# gm-board.net
KiCad netlist of a schematic drawn in EAGLE
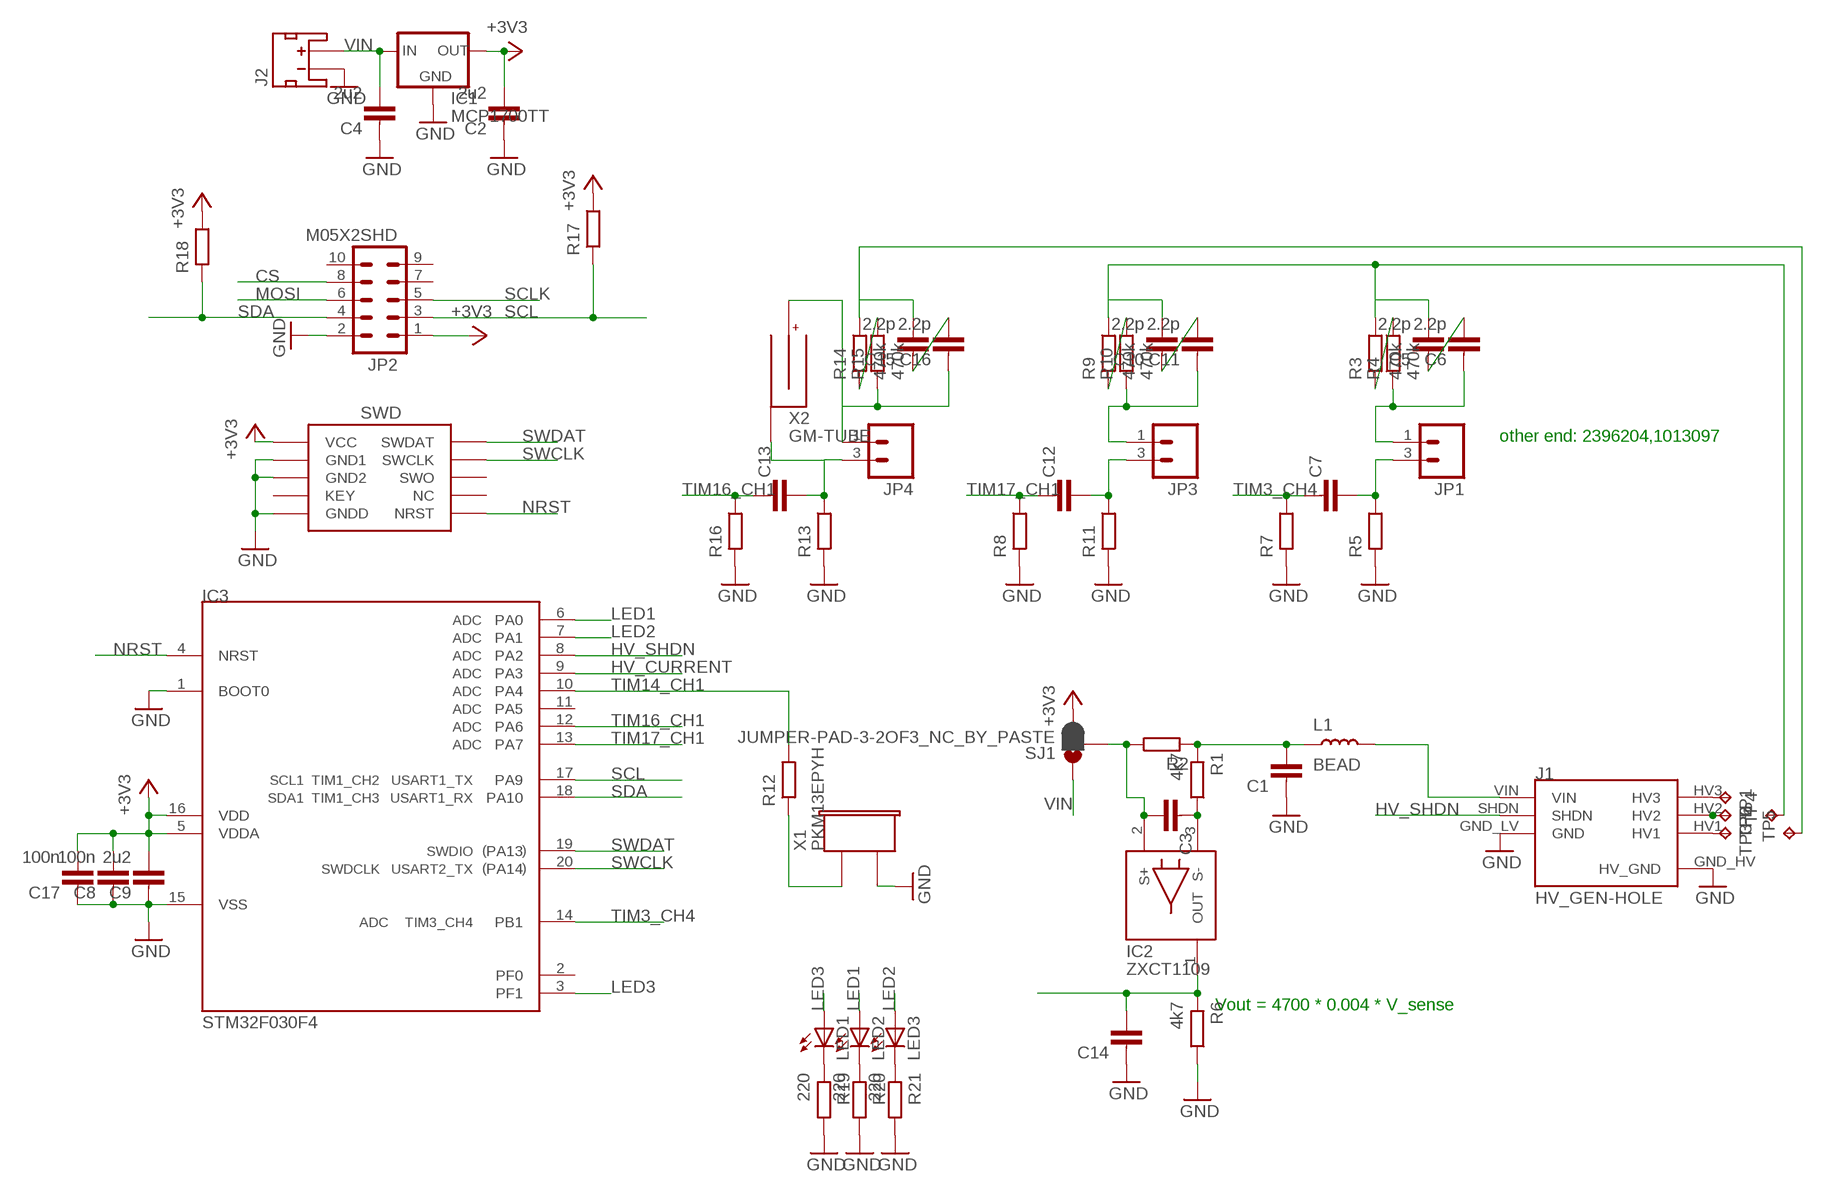
[diagram p0: schematic, sheet 1]

(export (version "E")
  (design (tool "Eeschema 10.0.6"))
  (components
    (comp (ref "C1")
      (value "CAPACITOR0603-N")
      (footprint "eagle-import:C0603-N")
      (libsource (lib "eagle-import") (part "CAPACITOR0603-N"))
    )
    (comp (ref "C2")
      (value "2u2")
      (footprint "eagle-import:C0603-N")
      (libsource (lib "eagle-import") (part "CAPACITOR0603-N"))
    )
    (comp (ref "C3")
      (value "CAPACITOR0603-N")
      (footprint "eagle-import:C0603-N")
      (libsource (lib "eagle-import") (part "CAPACITOR0603-N"))
    )
    (comp (ref "C4")
      (value "2u2")
      (footprint "eagle-import:C0603-N")
      (libsource (lib "eagle-import") (part "CAPACITOR0603-N"))
    )
    (comp (ref "C5")
      (value "2.2p")
      (footprint "eagle-import:C0805-N")
      (libsource (lib "eagle-import") (part "CAPACITOR0805-N"))
    )
    (comp (ref "C6")
      (value "2.2p")
      (footprint "eagle-import:C0805-N")
      (libsource (lib "eagle-import") (part "CAPACITOR0805-N"))
    )
    (comp (ref "C7")
      (value "CAPACITOR0603-N")
      (footprint "eagle-import:C0603-N")
      (libsource (lib "eagle-import") (part "CAPACITOR0603-N"))
    )
    (comp (ref "C8")
      (value "100n")
      (footprint "eagle-import:C0603-N")
      (libsource (lib "eagle-import") (part "CAPACITOR0603-N"))
    )
    (comp (ref "C9")
      (value "2u2")
      (footprint "eagle-import:C0603-N")
      (libsource (lib "eagle-import") (part "CAPACITOR0603-N"))
    )
    (comp (ref "C10")
      (value "2.2p")
      (footprint "eagle-import:C0805-N")
      (libsource (lib "eagle-import") (part "CAPACITOR0805-N"))
    )
    (comp (ref "C11")
      (value "2.2p")
      (footprint "eagle-import:C0805-N")
      (libsource (lib "eagle-import") (part "CAPACITOR0805-N"))
    )
    (comp (ref "C12")
      (value "CAPACITOR0603-N")
      (footprint "eagle-import:C0603-N")
      (libsource (lib "eagle-import") (part "CAPACITOR0603-N"))
    )
    (comp (ref "C13")
      (value "CAPACITOR0603-N")
      (footprint "eagle-import:C0603-N")
      (libsource (lib "eagle-import") (part "CAPACITOR0603-N"))
    )
    (comp (ref "C14")
      (value "CAPACITOR0603-N")
      (footprint "eagle-import:C0603-N")
      (libsource (lib "eagle-import") (part "CAPACITOR0603-N"))
    )
    (comp (ref "C15")
      (value "2.2p")
      (footprint "eagle-import:C0805-N")
      (libsource (lib "eagle-import") (part "CAPACITOR0805-N"))
    )
    (comp (ref "C16")
      (value "2.2p")
      (footprint "eagle-import:C0805-N")
      (libsource (lib "eagle-import") (part "CAPACITOR0805-N"))
    )
    (comp (ref "C17")
      (value "100n")
      (footprint "eagle-import:C0603-N")
      (libsource (lib "eagle-import") (part "CAPACITOR0603-N"))
    )
    (comp (ref "IC1")
      (value "MCP1700TT")
      (footprint "eagle-import:SOT23")
      (libsource (lib "eagle-import") (part "MCP1700TT"))
    )
    (comp (ref "IC2")
      (value "ZXCT1109")
      (footprint "eagle-import:SOT23")
      (libsource (lib "eagle-import") (part "ZXCT1109"))
    )
    (comp (ref "IC3")
      (value "STM32F030F4")
      (footprint "eagle-import:TSSOP20")
      (libsource (lib "eagle-import") (part "STM32F030F4"))
    )
    (comp (ref "J1")
      (value "HV_GEN-HOLE")
      (footprint "eagle-import:BRD-LAYOUT2")
      (libsource (lib "eagle-import") (part "HV_GEN-HOLE"))
    )
    (comp (ref "J2")
      (value "JST_2MM_MALE_TH-NT")
      (footprint "eagle-import:JST-2-TH-NOTEXT")
      (libsource (lib "eagle-import") (part "JST_2MM_MALE_TH-NT"))
    )
    (comp (ref "J3")
      (value "SWD_SHROUD")
      (footprint "eagle-import:SWD_PTH_SHROUD")
      (libsource (lib "eagle-import") (part "SWD_SHROUD"))
    )
    (comp (ref "JP1")
      (value "M02-HV")
      (footprint "eagle-import:M03-HV")
      (libsource (lib "eagle-import") (part "M02-HV"))
    )
    (comp (ref "JP2")
      (value "M05X2SHD")
      (footprint "eagle-import:2X5-SHROUDED")
      (libsource (lib "eagle-import") (part "M05X2SHD"))
    )
    (comp (ref "JP3")
      (value "M02-HV")
      (footprint "eagle-import:M03-HV")
      (libsource (lib "eagle-import") (part "M02-HV"))
    )
    (comp (ref "JP4")
      (value "M02-HV")
      (footprint "eagle-import:M03-HV")
      (libsource (lib "eagle-import") (part "M02-HV"))
    )
    (comp (ref "L1")
      (value "BEAD")
      (footprint "eagle-import:L0603-N")
      (libsource (lib "eagle-import") (part "INDUCTOR0603-N"))
    )
    (comp (ref "LED1")
      (value "LEDCHIPLED_0603")
      (footprint "eagle-import:CHIPLED_0603")
      (libsource (lib "eagle-import") (part "LEDCHIPLED_0603"))
    )
    (comp (ref "LED2")
      (value "LEDCHIPLED_0603")
      (footprint "eagle-import:CHIPLED_0603")
      (libsource (lib "eagle-import") (part "LEDCHIPLED_0603"))
    )
    (comp (ref "LED3")
      (value "LEDCHIPLED_0603")
      (footprint "eagle-import:CHIPLED_0603")
      (libsource (lib "eagle-import") (part "LEDCHIPLED_0603"))
    )
    (comp (ref "R1")
      (value "4k7")
      (footprint "eagle-import:R0603-N")
      (libsource (lib "eagle-import") (part "RESISTOR0603-N"))
    )
    (comp (ref "R2")
      (value "RESISTOR0603-N")
      (footprint "eagle-import:R0603-N")
      (libsource (lib "eagle-import") (part "RESISTOR0603-N"))
    )
    (comp (ref "R3")
      (value "470k")
      (footprint "eagle-import:R1206-N")
      (libsource (lib "eagle-import") (part "RESISTOR1206-N"))
    )
    (comp (ref "R4")
      (value "470k")
      (footprint "eagle-import:R1206-N")
      (libsource (lib "eagle-import") (part "RESISTOR1206-N"))
    )
    (comp (ref "R5")
      (value "RESISTOR0603-N")
      (footprint "eagle-import:R0603-N")
      (libsource (lib "eagle-import") (part "RESISTOR0603-N"))
    )
    (comp (ref "R6")
      (value "4k7")
      (footprint "eagle-import:R0603-N")
      (libsource (lib "eagle-import") (part "RESISTOR0603-N"))
    )
    (comp (ref "R7")
      (value "RESISTOR0603-N")
      (footprint "eagle-import:R0603-N")
      (libsource (lib "eagle-import") (part "RESISTOR0603-N"))
    )
    (comp (ref "R8")
      (value "RESISTOR0603-N")
      (footprint "eagle-import:R0603-N")
      (libsource (lib "eagle-import") (part "RESISTOR0603-N"))
    )
    (comp (ref "R9")
      (value "470k")
      (footprint "eagle-import:R1206-N")
      (libsource (lib "eagle-import") (part "RESISTOR1206-N"))
    )
    (comp (ref "R10")
      (value "470k")
      (footprint "eagle-import:R1206-N")
      (libsource (lib "eagle-import") (part "RESISTOR1206-N"))
    )
    (comp (ref "R11")
      (value "RESISTOR0603-N")
      (footprint "eagle-import:R0603-N")
      (libsource (lib "eagle-import") (part "RESISTOR0603-N"))
    )
    (comp (ref "R12")
      (value "RESISTOR0603-N")
      (footprint "eagle-import:R0603-N")
      (libsource (lib "eagle-import") (part "RESISTOR0603-N"))
    )
    (comp (ref "R13")
      (value "RESISTOR0603-N")
      (footprint "eagle-import:R0603-N")
      (libsource (lib "eagle-import") (part "RESISTOR0603-N"))
    )
    (comp (ref "R14")
      (value "470k")
      (footprint "eagle-import:R1206-N")
      (libsource (lib "eagle-import") (part "RESISTOR1206-N"))
    )
    (comp (ref "R15")
      (value "470k")
      (footprint "eagle-import:R1206-N")
      (libsource (lib "eagle-import") (part "RESISTOR1206-N"))
    )
    (comp (ref "R16")
      (value "RESISTOR0603-N")
      (footprint "eagle-import:R0603-N")
      (libsource (lib "eagle-import") (part "RESISTOR0603-N"))
    )
    (comp (ref "R17")
      (value "RESISTOR0603-N")
      (footprint "eagle-import:R0603-N")
      (libsource (lib "eagle-import") (part "RESISTOR0603-N"))
    )
    (comp (ref "R18")
      (value "RESISTOR0603-N")
      (footprint "eagle-import:R0603-N")
      (libsource (lib "eagle-import") (part "RESISTOR0603-N"))
    )
    (comp (ref "R19")
      (value "220")
      (footprint "eagle-import:R0603-N")
      (libsource (lib "eagle-import") (part "RESISTOR0603-N"))
    )
    (comp (ref "R20")
      (value "220")
      (footprint "eagle-import:R0603-N")
      (libsource (lib "eagle-import") (part "RESISTOR0603-N"))
    )
    (comp (ref "R21")
      (value "220")
      (footprint "eagle-import:R0603-N")
      (libsource (lib "eagle-import") (part "RESISTOR0603-N"))
    )
    (comp (ref "SJ1")
      (value "JUMPER-PAD-3-2OF3_NC_BY_PASTE")
      (footprint "eagle-import:PAD-JUMPER-3-2OF3_NC_BY_PASTE_YES_SILK_FULL_BOX")
      (libsource (lib "eagle-import") (part "JUMPER-PAD-3-2OF3_NC_BY_PASTE"))
    )
    (comp (ref "TP1")
      (value "TPTP09R")
      (footprint "eagle-import:TP09R")
      (libsource (lib "eagle-import") (part "TPTP09R"))
    )
    (comp (ref "TP2")
      (value "TPTP09R")
      (footprint "eagle-import:TP09R")
      (libsource (lib "eagle-import") (part "TPTP09R"))
    )
    (comp (ref "TP3")
      (value "TPTP09R")
      (footprint "eagle-import:TP09R")
      (libsource (lib "eagle-import") (part "TPTP09R"))
    )
    (comp (ref "TP4")
      (value "TPTP09R")
      (footprint "eagle-import:TP09R")
      (libsource (lib "eagle-import") (part "TPTP09R"))
    )
    (comp (ref "TP5")
      (value "TPTP09R")
      (footprint "eagle-import:TP09R")
      (libsource (lib "eagle-import") (part "TPTP09R"))
    )
    (comp (ref "TP6")
      (value "TPTP09R")
      (footprint "eagle-import:TP09R")
      (libsource (lib "eagle-import") (part "TPTP09R"))
    )
    (comp (ref "X1")
      (value "PKM13EPYH")
      (footprint "eagle-import:PKM13EPYH")
      (libsource (lib "eagle-import") (part "PKM13EPYH"))
    )
    (comp (ref "X2")
      (value "GM-TUBE")
      (footprint "eagle-import:GM-TUBE")
      (libsource (lib "eagle-import") (part "GM-TUBE"))
    )
  )
  (nets
    (net (code "1") (name "+3V3") (class "Default")
      (node (ref "C17") (pin "2") (pinfunction "2_2") (pintype "passive"))
      (node (ref "C2") (pin "2") (pinfunction "2_2") (pintype "passive"))
      (node (ref "C8") (pin "2") (pinfunction "2_2") (pintype "passive"))
      (node (ref "C9") (pin "2") (pinfunction "2_2") (pintype "passive"))
      (node (ref "IC1") (pin "2") (pinfunction "OUT_2") (pintype "passive"))
      (node (ref "IC3") (pin "16") (pinfunction "VDD_16") (pintype "power_in"))
      (node (ref "IC3") (pin "5") (pinfunction "VDDA_5") (pintype "power_in"))
      (node (ref "J3") (pin "1") (pinfunction "VCC_1") (pintype "power_in"))
      (node (ref "JP2") (pin "1") (pinfunction "1_1") (pintype "passive"))
      (node (ref "R17") (pin "2") (pinfunction "P$2_2") (pintype "passive"))
      (node (ref "R18") (pin "2") (pinfunction "P$2_2") (pintype "passive"))
      (node (ref "SJ1") (pin "3") (pinfunction "3_3") (pintype "passive"))
    )
    (net (code "2") (name "/CS") (class "Default")
      (node (ref "JP2") (pin "8") (pinfunction "8_8") (pintype "passive"))
    )
    (net (code "3") (name "/HV_CURRENT") (class "Default")
      (node (ref "C14") (pin "2") (pinfunction "2_2") (pintype "passive"))
      (node (ref "IC2") (pin "1") (pinfunction "OUT_1") (pintype "output"))
      (node (ref "IC3") (pin "9") (pinfunction "PA3_9") (pintype "bidirectional"))
      (node (ref "R6") (pin "1") (pinfunction "P$1_1") (pintype "passive"))
    )
    (net (code "4") (name "/HV_SHDN") (class "Default")
      (node (ref "IC3") (pin "8") (pinfunction "PA2_8") (pintype "bidirectional"))
      (node (ref "J1") (pin "SHDN") (pinfunction "SHDN_SHDN") (pintype "bidirectional"))
    )
    (net (code "5") (name "/LED1") (class "Default")
      (node (ref "IC3") (pin "6") (pinfunction "PA0_6") (pintype "bidirectional"))
      (node (ref "LED2") (pin "A") (pinfunction "A_A") (pintype "passive"))
    )
    (net (code "6") (name "/LED2") (class "Default")
      (node (ref "IC3") (pin "7") (pinfunction "PA1_7") (pintype "bidirectional"))
      (node (ref "LED3") (pin "A") (pinfunction "A_A") (pintype "passive"))
    )
    (net (code "7") (name "/LED3") (class "Default")
      (node (ref "IC3") (pin "3") (pinfunction "PF1_3") (pintype "bidirectional"))
      (node (ref "LED1") (pin "A") (pinfunction "A_A") (pintype "passive"))
    )
    (net (code "8") (name "/MOSI") (class "Default")
      (node (ref "JP2") (pin "6") (pinfunction "6_6") (pintype "passive"))
    )
    (net (code "9") (name "/NRST") (class "Default")
      (node (ref "IC3") (pin "4") (pinfunction "NRST_4") (pintype "input"))
      (node (ref "J3") (pin "10") (pinfunction "NRST_10") (pintype "bidirectional"))
    )
    (net (code "10") (name "/SCL") (class "Default")
      (node (ref "IC3") (pin "17") (pinfunction "PA9_17") (pintype "bidirectional"))
      (node (ref "JP2") (pin "3") (pinfunction "3_3") (pintype "passive"))
      (node (ref "R17") (pin "1") (pinfunction "P$1_1") (pintype "passive"))
    )
    (net (code "11") (name "/SCLK") (class "Default")
      (node (ref "JP2") (pin "5") (pinfunction "5_5") (pintype "passive"))
    )
    (net (code "12") (name "/SDA") (class "Default")
      (node (ref "IC3") (pin "18") (pinfunction "PA10_18") (pintype "bidirectional"))
      (node (ref "JP2") (pin "4") (pinfunction "4_4") (pintype "passive"))
      (node (ref "R18") (pin "1") (pinfunction "P$1_1") (pintype "passive"))
    )
    (net (code "13") (name "/SWCLK") (class "Default")
      (node (ref "IC3") (pin "20") (pinfunction "PA14_20") (pintype "bidirectional"))
      (node (ref "J3") (pin "4") (pinfunction "SWCLK_4") (pintype "bidirectional"))
    )
    (net (code "14") (name "/SWDAT") (class "Default")
      (node (ref "IC3") (pin "19") (pinfunction "PA13_19") (pintype "bidirectional"))
      (node (ref "J3") (pin "2") (pinfunction "SWDAT_2") (pintype "bidirectional"))
    )
    (net (code "15") (name "/TIM3_CH4") (class "Default")
      (node (ref "C7") (pin "1") (pinfunction "1_1") (pintype "passive"))
      (node (ref "IC3") (pin "14") (pinfunction "PB1_14") (pintype "bidirectional"))
      (node (ref "R7") (pin "2") (pinfunction "P$2_2") (pintype "passive"))
    )
    (net (code "16") (name "/TIM14_CH1") (class "Default")
      (node (ref "IC3") (pin "10") (pinfunction "PA4_10") (pintype "bidirectional"))
      (node (ref "R12") (pin "2") (pinfunction "P$2_2") (pintype "passive"))
    )
    (net (code "17") (name "/TIM16_CH1") (class "Default")
      (node (ref "C13") (pin "1") (pinfunction "1_1") (pintype "passive"))
      (node (ref "IC3") (pin "12") (pinfunction "PA6_12") (pintype "bidirectional"))
      (node (ref "R16") (pin "2") (pinfunction "P$2_2") (pintype "passive"))
    )
    (net (code "18") (name "/TIM17_CH1") (class "Default")
      (node (ref "C12") (pin "1") (pinfunction "1_1") (pintype "passive"))
      (node (ref "IC3") (pin "13") (pinfunction "PA7_13") (pintype "bidirectional"))
      (node (ref "R8") (pin "2") (pinfunction "P$2_2") (pintype "passive"))
    )
    (net (code "19") (name "/VIN") (class "Default")
      (node (ref "C4") (pin "2") (pinfunction "2_2") (pintype "passive"))
      (node (ref "IC1") (pin "3") (pinfunction "IN_3") (pintype "input"))
      (node (ref "J2") (pin "1") (pinfunction "+_1") (pintype "bidirectional"))
      (node (ref "SJ1") (pin "1") (pinfunction "1_1") (pintype "passive"))
    )
    (net (code "20") (name "GND") (class "Default")
      (node (ref "C1") (pin "1") (pinfunction "1_1") (pintype "passive"))
      (node (ref "C14") (pin "1") (pinfunction "1_1") (pintype "passive"))
      (node (ref "C17") (pin "1") (pinfunction "1_1") (pintype "passive"))
      (node (ref "C2") (pin "1") (pinfunction "1_1") (pintype "passive"))
      (node (ref "C4") (pin "1") (pinfunction "1_1") (pintype "passive"))
      (node (ref "C8") (pin "1") (pinfunction "1_1") (pintype "passive"))
      (node (ref "C9") (pin "1") (pinfunction "1_1") (pintype "passive"))
      (node (ref "IC1") (pin "1") (pinfunction "GND_1") (pintype "input"))
      (node (ref "IC3") (pin "1") (pinfunction "BOOT0_1") (pintype "input"))
      (node (ref "IC3") (pin "15") (pinfunction "VSS_15") (pintype "power_in"))
      (node (ref "J1") (pin "GND_HV") (pinfunction "HV_GND_GND_HV") (pintype "bidirectional"))
      (node (ref "J1") (pin "GND_LV") (pinfunction "GND_GND_LV") (pintype "bidirectional"))
      (node (ref "J2") (pin "2") (pinfunction "-_2") (pintype "bidirectional"))
      (node (ref "J3") (pin "3") (pinfunction "GND1_3") (pintype "power_in"))
      (node (ref "J3") (pin "5") (pinfunction "GND2_5") (pintype "power_in"))
      (node (ref "J3") (pin "9") (pinfunction "GNDD_9") (pintype "power_in"))
      (node (ref "JP2") (pin "2") (pinfunction "2_2") (pintype "passive"))
      (node (ref "R11") (pin "1") (pinfunction "P$1_1") (pintype "passive"))
      (node (ref "R13") (pin "1") (pinfunction "P$1_1") (pintype "passive"))
      (node (ref "R16") (pin "1") (pinfunction "P$1_1") (pintype "passive"))
      (node (ref "R19") (pin "2") (pinfunction "P$2_2") (pintype "passive"))
      (node (ref "R20") (pin "2") (pinfunction "P$2_2") (pintype "passive"))
      (node (ref "R21") (pin "2") (pinfunction "P$2_2") (pintype "passive"))
      (node (ref "R5") (pin "1") (pinfunction "P$1_1") (pintype "passive"))
      (node (ref "R6") (pin "2") (pinfunction "P$2_2") (pintype "passive"))
      (node (ref "R7") (pin "1") (pinfunction "P$1_1") (pintype "passive"))
      (node (ref "R8") (pin "1") (pinfunction "P$1_1") (pintype "passive"))
      (node (ref "X1") (pin "2") (pinfunction "2_2") (pintype "bidirectional"))
    )
    (net (code "21") (name "Net-(C5-Pad1)") (class "Default")
      (node (ref "C5") (pin "1") (pinfunction "1_1") (pintype "passive"))
      (node (ref "C6") (pin "2") (pinfunction "2_2") (pintype "passive"))
    )
    (net (code "22") (name "Net-(C10-Pad1)") (class "Default")
      (node (ref "C10") (pin "1") (pinfunction "1_1") (pintype "passive"))
      (node (ref "C11") (pin "2") (pinfunction "2_2") (pintype "passive"))
    )
    (net (code "23") (name "Net-(C15-Pad1)") (class "Default")
      (node (ref "C15") (pin "1") (pinfunction "1_1") (pintype "passive"))
      (node (ref "C16") (pin "2") (pinfunction "2_2") (pintype "passive"))
    )
    (net (code "24") (name "Net-(IC2-S+)") (class "Default")
      (node (ref "C3") (pin "2") (pinfunction "2_2") (pintype "passive"))
      (node (ref "IC2") (pin "2") (pinfunction "S+_2") (pintype "input"))
      (node (ref "R2") (pin "2") (pinfunction "P$2_2") (pintype "passive"))
      (node (ref "SJ1") (pin "2") (pinfunction "2_2") (pintype "passive"))
    )
    (net (code "25") (name "Net-(IC2-S-)") (class "Default")
      (node (ref "C3") (pin "1") (pinfunction "1_1") (pintype "passive"))
      (node (ref "IC2") (pin "3") (pinfunction "S-_3") (pintype "input"))
      (node (ref "R1") (pin "2") (pinfunction "P$2_2") (pintype "passive"))
    )
    (net (code "26") (name "Net-(J1-PadHV1)") (class "Default")
      (node (ref "J1") (pin "HV1") (pinfunction "HV1_HV1") (pintype "bidirectional"))
      (node (ref "TP3") (pin "TP") (pinfunction "TP_TP") (pintype "input"))
    )
    (net (code "27") (name "Net-(J1-PadHV2)") (class "Default")
      (node (ref "J1") (pin "HV2") (pinfunction "HV2_HV2") (pintype "bidirectional"))
      (node (ref "TP2") (pin "TP") (pinfunction "TP_TP") (pintype "input"))
      (node (ref "TP6") (pin "TP") (pinfunction "TP_TP") (pintype "input"))
    )
    (net (code "28") (name "Net-(J1-PadHV3)") (class "Default")
      (node (ref "J1") (pin "HV3") (pinfunction "HV3_HV3") (pintype "bidirectional"))
      (node (ref "TP1") (pin "TP") (pinfunction "TP_TP") (pintype "input"))
    )
    (net (code "29") (name "Net-(JP1-2)") (class "Default")
      (node (ref "C7") (pin "2") (pinfunction "2_2") (pintype "passive"))
      (node (ref "JP1") (pin "3") (pinfunction "2_3") (pintype "passive"))
      (node (ref "R5") (pin "2") (pinfunction "P$2_2") (pintype "passive"))
    )
    (net (code "30") (name "Net-(JP3-2)") (class "Default")
      (node (ref "C12") (pin "2") (pinfunction "2_2") (pintype "passive"))
      (node (ref "JP3") (pin "3") (pinfunction "2_3") (pintype "passive"))
      (node (ref "R11") (pin "2") (pinfunction "P$2_2") (pintype "passive"))
    )
    (net (code "31") (name "Net-(JP4-2)") (class "Default")
      (node (ref "C13") (pin "2") (pinfunction "2_2") (pintype "passive"))
      (node (ref "JP4") (pin "3") (pinfunction "2_3") (pintype "passive"))
      (node (ref "R13") (pin "2") (pinfunction "P$2_2") (pintype "passive"))
      (node (ref "X2") (pin "B1") (pinfunction "-_B1") (pintype "bidirectional"))
      (node (ref "X2") (pin "B2") (pinfunction "-_B2") (pintype "bidirectional"))
    )
    (net (code "32") (name "Net-(L1-P$1)") (class "Default")
      (node (ref "C1") (pin "2") (pinfunction "2_2") (pintype "passive"))
      (node (ref "L1") (pin "1") (pinfunction "P$1_1") (pintype "passive"))
      (node (ref "R1") (pin "1") (pinfunction "P$1_1") (pintype "passive"))
      (node (ref "R2") (pin "1") (pinfunction "P$1_1") (pintype "passive"))
    )
    (net (code "33") (name "Net-(L1-P$2)") (class "Default")
      (node (ref "J1") (pin "VIN") (pinfunction "VIN_VIN") (pintype "bidirectional"))
      (node (ref "L1") (pin "2") (pinfunction "P$2_2") (pintype "passive"))
    )
    (net (code "34") (name "Net-(R3-P$1)") (class "Default")
      (node (ref "R3") (pin "1") (pinfunction "P$1_1") (pintype "passive"))
      (node (ref "R4") (pin "2") (pinfunction "P$2_2") (pintype "passive"))
    )
    (net (code "35") (name "Net-(R3-P$2)") (class "Default")
      (node (ref "C10") (pin "2") (pinfunction "2_2") (pintype "passive"))
      (node (ref "C5") (pin "2") (pinfunction "2_2") (pintype "passive"))
      (node (ref "R3") (pin "2") (pinfunction "P$2_2") (pintype "passive"))
      (node (ref "R9") (pin "2") (pinfunction "P$2_2") (pintype "passive"))
      (node (ref "TP4") (pin "TP") (pinfunction "TP_TP") (pintype "input"))
    )
    (net (code "36") (name "Net-(R4-P$1)") (class "Default")
      (node (ref "C6") (pin "1") (pinfunction "1_1") (pintype "passive"))
      (node (ref "JP1") (pin "1") (pinfunction "1_1") (pintype "passive"))
      (node (ref "R4") (pin "1") (pinfunction "P$1_1") (pintype "passive"))
    )
    (net (code "37") (name "Net-(R10-P$1)") (class "Default")
      (node (ref "C11") (pin "1") (pinfunction "1_1") (pintype "passive"))
      (node (ref "JP3") (pin "1") (pinfunction "1_1") (pintype "passive"))
      (node (ref "R10") (pin "1") (pinfunction "P$1_1") (pintype "passive"))
    )
    (net (code "38") (name "Net-(R10-P$2)") (class "Default")
      (node (ref "R10") (pin "2") (pinfunction "P$2_2") (pintype "passive"))
      (node (ref "R9") (pin "1") (pinfunction "P$1_1") (pintype "passive"))
    )
    (net (code "39") (name "Net-(R12-P$1)") (class "Default")
      (node (ref "R12") (pin "1") (pinfunction "P$1_1") (pintype "passive"))
      (node (ref "X1") (pin "1") (pinfunction "1_1") (pintype "bidirectional"))
    )
    (net (code "40") (name "Net-(R14-P$1)") (class "Default")
      (node (ref "R14") (pin "1") (pinfunction "P$1_1") (pintype "passive"))
      (node (ref "R15") (pin "2") (pinfunction "P$2_2") (pintype "passive"))
    )
    (net (code "41") (name "Net-(R14-P$2)") (class "Default")
      (node (ref "C15") (pin "2") (pinfunction "2_2") (pintype "passive"))
      (node (ref "R14") (pin "2") (pinfunction "P$2_2") (pintype "passive"))
      (node (ref "TP5") (pin "TP") (pinfunction "TP_TP") (pintype "input"))
    )
    (net (code "42") (name "Net-(R15-P$1)") (class "Default")
      (node (ref "C16") (pin "1") (pinfunction "1_1") (pintype "passive"))
      (node (ref "JP4") (pin "1") (pinfunction "1_1") (pintype "passive"))
      (node (ref "R15") (pin "1") (pinfunction "P$1_1") (pintype "passive"))
      (node (ref "X2") (pin "A1") (pinfunction "+_A1") (pintype "bidirectional"))
      (node (ref "X2") (pin "A2") (pinfunction "+_A2") (pintype "bidirectional"))
    )
    (net (code "43") (name "Net-(R19-P$1)") (class "Default")
      (node (ref "LED1") (pin "C") (pinfunction "C_C") (pintype "passive"))
      (node (ref "R19") (pin "1") (pinfunction "P$1_1") (pintype "passive"))
    )
    (net (code "44") (name "Net-(R20-P$1)") (class "Default")
      (node (ref "LED2") (pin "C") (pinfunction "C_C") (pintype "passive"))
      (node (ref "R20") (pin "1") (pinfunction "P$1_1") (pintype "passive"))
    )
    (net (code "45") (name "Net-(R21-P$1)") (class "Default")
      (node (ref "LED3") (pin "C") (pinfunction "C_C") (pintype "passive"))
      (node (ref "R21") (pin "1") (pinfunction "P$1_1") (pintype "passive"))
    )
    (net (code "46") (name "unconnected-(IC3-PA5-Pad11)") (class "Default")
      (node (ref "IC3") (pin "11") (pinfunction "PA5_11") (pintype "bidirectional"))
    )
    (net (code "47") (name "unconnected-(IC3-PF0-Pad2)") (class "Default")
      (node (ref "IC3") (pin "2") (pinfunction "PF0_2") (pintype "bidirectional"))
    )
    (net (code "48") (name "unconnected-(J3-KEY-Pad7)") (class "Default")
      (node (ref "J3") (pin "7") (pinfunction "KEY_7") (pintype "bidirectional"))
    )
    (net (code "49") (name "unconnected-(J3-NC-Pad8)") (class "Default")
      (node (ref "J3") (pin "8") (pinfunction "NC_8") (pintype "no_connect"))
    )
    (net (code "50") (name "unconnected-(J3-SWO-Pad6)") (class "Default")
      (node (ref "J3") (pin "6") (pinfunction "SWO_6") (pintype "bidirectional"))
    )
    (net (code "51") (name "unconnected-(JP2-Pad7)") (class "Default")
      (node (ref "JP2") (pin "7") (pinfunction "7_7") (pintype "passive"))
    )
    (net (code "52") (name "unconnected-(JP2-Pad9)") (class "Default")
      (node (ref "JP2") (pin "9") (pinfunction "9_9") (pintype "passive"))
    )
    (net (code "53") (name "unconnected-(JP2-Pad10)") (class "Default")
      (node (ref "JP2") (pin "10") (pinfunction "10_10") (pintype "passive"))
    )
  )
)
